# 4_Channel_TVS_alternative.net
KiCad netlist of a schematic drawn in Altium Designer
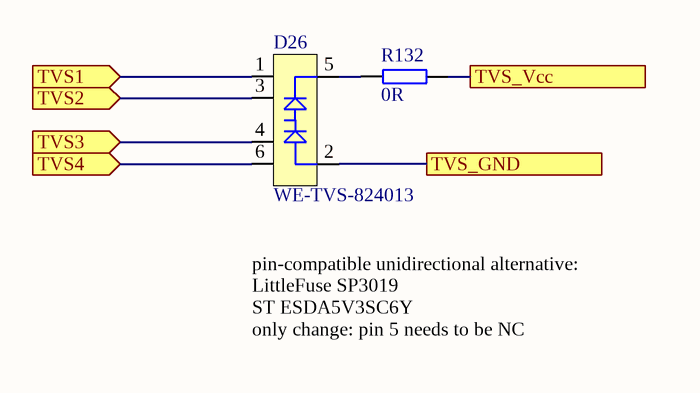
[diagram p0: 4_Channel_TVS_alternative.SchDoc]

(export (version "E")
  (design (tool "Eeschema 10.0.6"))
  (components
    (comp (ref "D26")
      (value "WE-TVS-824013")
      (footprint "SOT95P280X145-6N")
      (description "TVS/Clamp Diode Array 3.3/9V Quad SOT23-6")
      (libsource (lib "TE") (part "WE-TVS-824013"))
    )
    (comp (ref "R132")
      (value "0R")
      (footprint "RESC1608X55N_V")
      (description "WID SMD 0R 0,1W 1% TK100  BF 1608 (0603)")
      (fields (field (name "TOLERANCE") "1%"))
      (libsource (lib "TE") (part "RES"))
    )
  )
  (nets
    (net (code "1") (name "/TVS1") (class "Default")
      (node (ref "D26") (pin "1") (pinfunction "I/O1_1") (pintype "passive"))
    )
    (net (code "2") (name "/TVS2") (class "Default")
      (node (ref "D26") (pin "3") (pinfunction "I/O2_3") (pintype "passive"))
    )
    (net (code "3") (name "/TVS3") (class "Default")
      (node (ref "D26") (pin "4") (pinfunction "I/O3_4") (pintype "passive"))
    )
    (net (code "4") (name "/TVS4") (class "Default")
      (node (ref "D26") (pin "6") (pinfunction "I/O4_6") (pintype "passive"))
    )
    (net (code "5") (name "/TVS_GND") (class "Default")
      (node (ref "D26") (pin "2") (pinfunction "GND_2") (pintype "power_in"))
    )
    (net (code "6") (name "/TVS_Vcc") (class "Default")
      (node (ref "R132") (pin "1") (pinfunction "1_1") (pintype "passive"))
    )
    (net (code "7") (name "Net-(D26-VDD)") (class "Default")
      (node (ref "D26") (pin "5") (pinfunction "VDD_5") (pintype "power_in"))
      (node (ref "R132") (pin "2") (pinfunction "2_2") (pintype "passive"))
    )
  )
)
